# driverLED.net
KiCad netlist of a schematic drawn in EAGLE
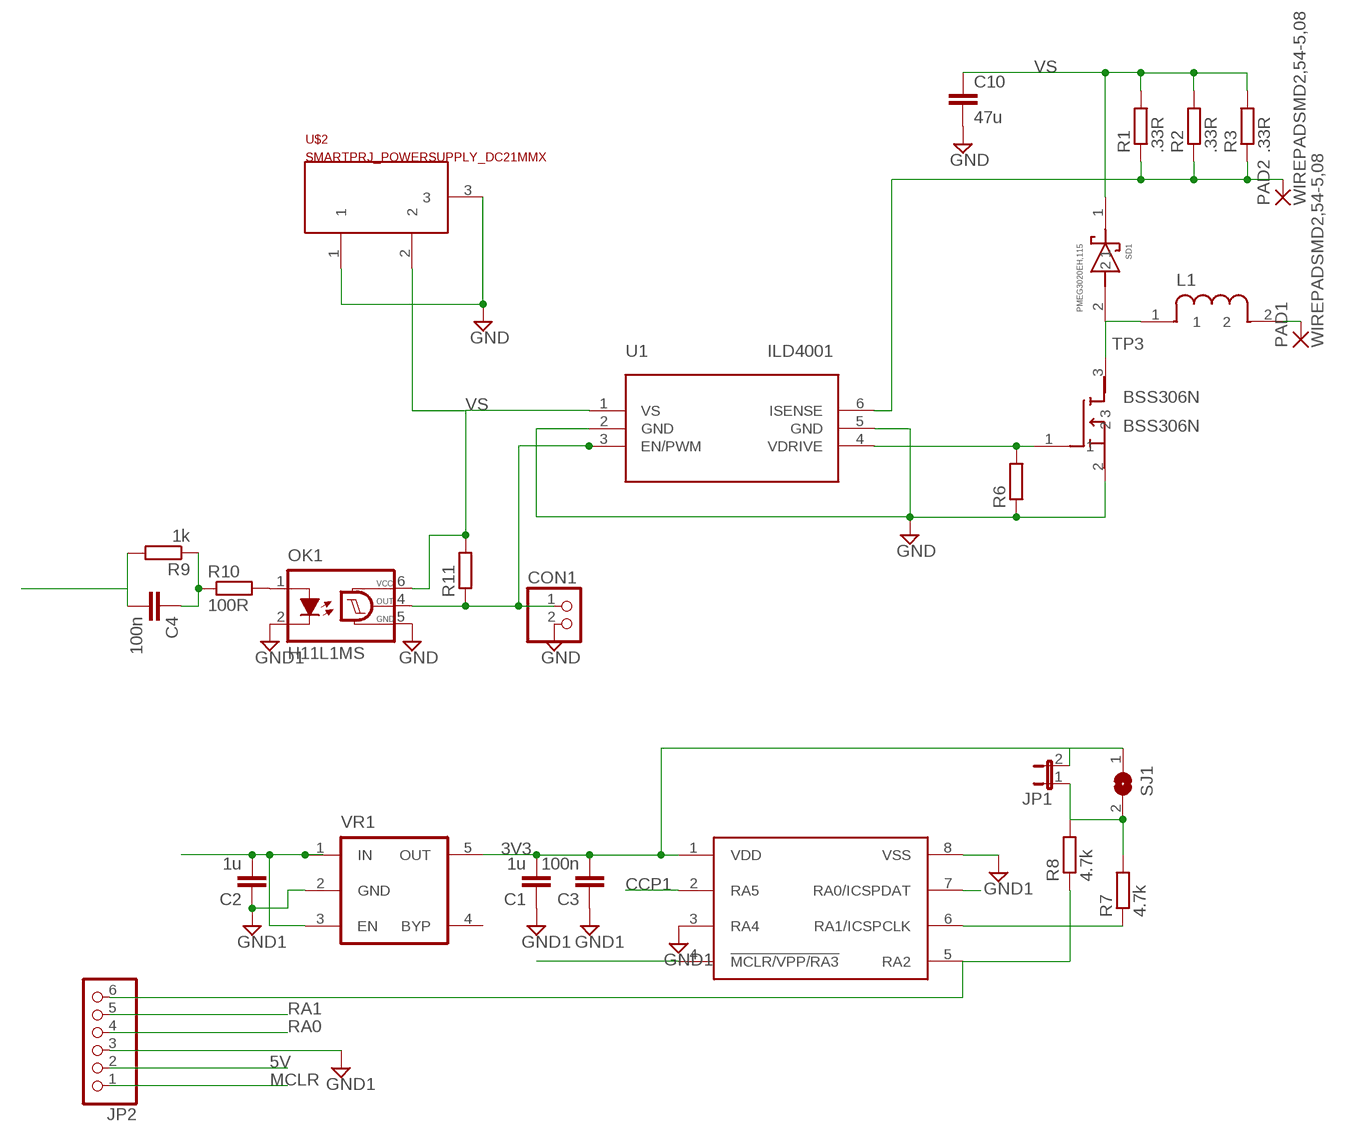
[diagram p0: schematic, sheet 1]

(export (version "E")
  (design (tool "Eeschema 10.0.6"))
  (components
    (comp (ref "BSS306N")
      (value "BSS306N")
      (footprint "eagle-import:SOT23")
      (libsource (lib "eagle-import") (part "BSS306N"))
    )
    (comp (ref "C1")
      (value "1u")
      (footprint "eagle-import:C0603")
      (libsource (lib "eagle-import") (part "C-EUC0603"))
    )
    (comp (ref "C2")
      (value "1u")
      (footprint "eagle-import:C0603")
      (libsource (lib "eagle-import") (part "C-EUC0603"))
    )
    (comp (ref "C3")
      (value "100n")
      (footprint "eagle-import:C0603")
      (libsource (lib "eagle-import") (part "C-EUC0603"))
    )
    (comp (ref "C4")
      (value "100n")
      (footprint "eagle-import:C0603")
      (libsource (lib "eagle-import") (part "C-EUC0603"))
    )
    (comp (ref "C10")
      (value "47u")
      (footprint "eagle-import:C1812")
      (libsource (lib "eagle-import") (part "C-EUC1812"))
    )
    (comp (ref "CON1")
      (value "PINHD-1X2")
      (footprint "eagle-import:1X02")
      (libsource (lib "eagle-import") (part "PINHD-1X2"))
    )
    (comp (ref "JP1")
      (value "JUMPER-2PTH")
      (footprint "eagle-import:1X02")
      (libsource (lib "eagle-import") (part "JUMPER-2PTH"))
    )
    (comp (ref "JP2")
      (value "PINHD-1X6")
      (footprint "eagle-import:1X06")
      (libsource (lib "eagle-import") (part "PINHD-1X6"))
    )
    (comp (ref "L1")
      (value "NR10050T470M")
      (footprint "eagle-import:NR10050T470M")
      (libsource (lib "eagle-import") (part "NR10050T470M"))
    )
    (comp (ref "OK1")
      (value "H11L1MS")
      (footprint "eagle-import:DIL6-SMD")
      (libsource (lib "eagle-import") (part "H11LMS1"))
    )
    (comp (ref "PAD1")
      (value "WIREPADSMD2,54-5,08")
      (footprint "eagle-import:SMD2,54-5,08")
      (libsource (lib "eagle-import") (part "WIREPADSMD2,54-5,08"))
    )
    (comp (ref "PAD2")
      (value "WIREPADSMD2,54-5,08")
      (footprint "eagle-import:SMD2,54-5,08")
      (libsource (lib "eagle-import") (part "WIREPADSMD2,54-5,08"))
    )
    (comp (ref "R1")
      (value ".33R")
      (footprint "eagle-import:R1206")
      (libsource (lib "eagle-import") (part "R-EU_R1206"))
    )
    (comp (ref "R2")
      (value ".33R")
      (footprint "eagle-import:R1206")
      (libsource (lib "eagle-import") (part "R-EU_R1206"))
    )
    (comp (ref "R3")
      (value ".33R")
      (footprint "eagle-import:R1206")
      (libsource (lib "eagle-import") (part "R-EU_R1206"))
    )
    (comp (ref "R6")
      (value "R-EU_R0603")
      (footprint "eagle-import:R0603")
      (libsource (lib "eagle-import") (part "resistor_R-EU_R0603"))
    )
    (comp (ref "R7")
      (value "4.7k")
      (footprint "eagle-import:R0603")
      (libsource (lib "eagle-import") (part "resistor_R-EU_R0603"))
    )
    (comp (ref "R8")
      (value "4.7k")
      (footprint "eagle-import:R0603")
      (libsource (lib "eagle-import") (part "resistor_R-EU_R0603"))
    )
    (comp (ref "R9")
      (value "1k")
      (footprint "eagle-import:R0603")
      (libsource (lib "eagle-import") (part "resistor_R-EU_R0603"))
    )
    (comp (ref "R10")
      (value "100R")
      (footprint "eagle-import:R0603")
      (libsource (lib "eagle-import") (part "R-EU_R0603"))
    )
    (comp (ref "R11")
      (value "R-EU_R0603")
      (footprint "eagle-import:R0603")
      (libsource (lib "eagle-import") (part "resistor_R-EU_R0603"))
    )
    (comp (ref "SD1")
      (value "PMEG3020EH,115")
      (footprint "eagle-import:SOD123F")
      (libsource (lib "eagle-import") (part "PMEG3020EH,115"))
    )
    (comp (ref "SJ1")
      (value "JUMPER_SJ")
      (footprint "eagle-import:JUMPER_SJ")
      (libsource (lib "eagle-import") (part "JUMPER_SJ"))
    )
    (comp (ref "U$1")
      (value "PIC12F1822")
      (footprint "eagle-import:8-SOIC")
      (libsource (lib "eagle-import") (part "PIC12F1822"))
    )
    (comp (ref "U$2")
      (value "SMARTPRJ_POWERSUPPLY_DC21MMX")
      (footprint "eagle-import:SMARTPRJ_POWERSUPPLY_DC-21MM")
      (libsource (lib "eagle-import") (part "SMARTPRJ_POWERSUPPLY_DC21MMX"))
    )
    (comp (ref "U1")
      (value "ILD4001")
      (footprint "eagle-import:SC74")
      (libsource (lib "eagle-import") (part "ILD4001"))
    )
    (comp (ref "VR1")
      (value "MIC5205")
      (footprint "eagle-import:SOT-23-5")
      (libsource (lib "eagle-import") (part "MIC5205"))
    )
  )
  (nets
    (net (code "1") (name "/3V3") (class "Default")
      (node (ref "C1") (pin "2") (pinfunction "2_2") (pintype "passive"))
      (node (ref "C3") (pin "2") (pinfunction "2_2") (pintype "passive"))
      (node (ref "JP1") (pin "2") (pinfunction "2_2") (pintype "passive"))
      (node (ref "SJ1") (pin "1") (pinfunction "1_1") (pintype "passive"))
      (node (ref "U$1") (pin "1") (pinfunction "VDD_1") (pintype "bidirectional"))
      (node (ref "VR1") (pin "5") (pinfunction "OUT_5") (pintype "bidirectional"))
    )
    (net (code "2") (name "/5V") (class "Default")
      (node (ref "C2") (pin "2") (pinfunction "2_2") (pintype "passive"))
      (node (ref "JP2") (pin "2") (pinfunction "2_2") (pintype "passive"))
      (node (ref "VR1") (pin "1") (pinfunction "IN_1") (pintype "bidirectional"))
      (node (ref "VR1") (pin "3") (pinfunction "EN_3") (pintype "bidirectional"))
    )
    (net (code "3") (name "/CCP1") (class "Default")
      (node (ref "C4") (pin "2") (pinfunction "2_2") (pintype "passive"))
      (node (ref "R9") (pin "2") (pinfunction "2_2") (pintype "passive"))
      (node (ref "U$1") (pin "2") (pinfunction "RA5_2") (pintype "bidirectional"))
    )
    (net (code "4") (name "/MCLR") (class "Default")
      (node (ref "JP2") (pin "1") (pinfunction "1_1") (pintype "passive"))
      (node (ref "U$1") (pin "4") (pinfunction "~{MCLR/VPP/RA3}_4") (pintype "bidirectional"))
    )
    (net (code "5") (name "/RA0") (class "Default")
      (node (ref "JP2") (pin "4") (pinfunction "4_4") (pintype "passive"))
      (node (ref "U$1") (pin "7") (pinfunction "RA0/ICSPDAT_7") (pintype "bidirectional"))
    )
    (net (code "6") (name "/RA1") (class "Default")
      (node (ref "JP2") (pin "5") (pinfunction "5_5") (pintype "passive"))
      (node (ref "R7") (pin "1") (pinfunction "1_1") (pintype "passive"))
      (node (ref "U$1") (pin "6") (pinfunction "RA1/ICSPCLK_6") (pintype "bidirectional"))
    )
    (net (code "7") (name "/TP3") (class "Default")
      (node (ref "BSS306N") (pin "3") (pinfunction "3_3") (pintype "bidirectional"))
      (node (ref "L1") (pin "1") (pinfunction "1_1") (pintype "bidirectional"))
      (node (ref "SD1") (pin "2") (pinfunction "2_2") (pintype "bidirectional"))
    )
    (net (code "8") (name "/VS") (class "Default")
      (node (ref "C10") (pin "1") (pinfunction "1_1") (pintype "passive"))
      (node (ref "OK1") (pin "6") (pinfunction "VCC_6") (pintype "power_in"))
      (node (ref "R1") (pin "2") (pinfunction "2_2") (pintype "passive"))
      (node (ref "R11") (pin "2") (pinfunction "2_2") (pintype "passive"))
      (node (ref "R2") (pin "2") (pinfunction "2_2") (pintype "passive"))
      (node (ref "R3") (pin "2") (pinfunction "2_2") (pintype "passive"))
      (node (ref "SD1") (pin "1") (pinfunction "1_1") (pintype "bidirectional"))
      (node (ref "U$2") (pin "2") (pinfunction "2_2") (pintype "power_in"))
      (node (ref "U1") (pin "1") (pinfunction "VS_1") (pintype "bidirectional"))
    )
    (net (code "9") (name "GND") (class "Default")
      (node (ref "BSS306N") (pin "2") (pinfunction "2_2") (pintype "bidirectional"))
      (node (ref "C10") (pin "2") (pinfunction "2_2") (pintype "passive"))
      (node (ref "CON1") (pin "2") (pinfunction "2_2") (pintype "passive"))
      (node (ref "OK1") (pin "5") (pinfunction "GND_5") (pintype "power_in"))
      (node (ref "R6") (pin "1") (pinfunction "1_1") (pintype "passive"))
      (node (ref "U$2") (pin "1") (pinfunction "1_1") (pintype "power_in"))
      (node (ref "U$2") (pin "3") (pinfunction "3_3") (pintype "power_in"))
      (node (ref "U1") (pin "2") (pinfunction "GND_2") (pintype "bidirectional"))
      (node (ref "U1") (pin "5") (pinfunction "GND_5") (pintype "bidirectional"))
    )
    (net (code "10") (name "GND1") (class "Default")
      (node (ref "C1") (pin "1") (pinfunction "1_1") (pintype "passive"))
      (node (ref "C2") (pin "1") (pinfunction "1_1") (pintype "passive"))
      (node (ref "C3") (pin "1") (pinfunction "1_1") (pintype "passive"))
      (node (ref "JP2") (pin "3") (pinfunction "3_3") (pintype "passive"))
      (node (ref "OK1") (pin "2") (pinfunction "C_2") (pintype "passive"))
      (node (ref "U$1") (pin "3") (pinfunction "RA4_3") (pintype "bidirectional"))
      (node (ref "U$1") (pin "8") (pinfunction "VSS_8") (pintype "bidirectional"))
      (node (ref "VR1") (pin "2") (pinfunction "GND_2") (pintype "bidirectional"))
    )
    (net (code "11") (name "Net-(C4-Pad1)") (class "Default")
      (node (ref "C4") (pin "1") (pinfunction "1_1") (pintype "passive"))
      (node (ref "R10") (pin "1") (pinfunction "1_1") (pintype "passive"))
      (node (ref "R9") (pin "1") (pinfunction "1_1") (pintype "passive"))
    )
    (net (code "12") (name "Net-(JP1-Pad1)") (class "Default")
      (node (ref "JP1") (pin "1") (pinfunction "1_1") (pintype "passive"))
      (node (ref "R7") (pin "2") (pinfunction "2_2") (pintype "passive"))
      (node (ref "R8") (pin "2") (pinfunction "2_2") (pintype "passive"))
      (node (ref "SJ1") (pin "2") (pinfunction "2_2") (pintype "passive"))
    )
    (net (code "13") (name "Net-(OK1-A)") (class "Default")
      (node (ref "OK1") (pin "1") (pinfunction "A_1") (pintype "passive"))
      (node (ref "R10") (pin "2") (pinfunction "2_2") (pintype "passive"))
    )
    (net (code "14") (name "Net-(OK1-OUT)") (class "Default")
      (node (ref "CON1") (pin "1") (pinfunction "1_1") (pintype "passive"))
      (node (ref "OK1") (pin "4") (pinfunction "OUT_4") (pintype "output"))
      (node (ref "R11") (pin "1") (pinfunction "1_1") (pintype "passive"))
      (node (ref "U1") (pin "3") (pinfunction "EN/PWM_3") (pintype "bidirectional"))
    )
    (net (code "15") (name "Net-(PAD1-P)") (class "Default")
      (node (ref "L1") (pin "2") (pinfunction "2_2") (pintype "bidirectional"))
      (node (ref "PAD1") (pin "1") (pinfunction "P_1") (pintype "passive"))
    )
    (net (code "16") (name "Net-(PAD2-P)") (class "Default")
      (node (ref "PAD2") (pin "1") (pinfunction "P_1") (pintype "passive"))
      (node (ref "R1") (pin "1") (pinfunction "1_1") (pintype "passive"))
      (node (ref "R2") (pin "1") (pinfunction "1_1") (pintype "passive"))
      (node (ref "R3") (pin "1") (pinfunction "1_1") (pintype "passive"))
      (node (ref "U1") (pin "6") (pinfunction "ISENSE_6") (pintype "bidirectional"))
    )
    (net (code "17") (name "Net-(U$1-RA2)") (class "Default")
      (node (ref "JP2") (pin "6") (pinfunction "6_6") (pintype "passive"))
      (node (ref "R8") (pin "1") (pinfunction "1_1") (pintype "passive"))
      (node (ref "U$1") (pin "5") (pinfunction "RA2_5") (pintype "bidirectional"))
    )
    (net (code "18") (name "Net-(U1-VDRIVE)") (class "Default")
      (node (ref "BSS306N") (pin "1") (pinfunction "1_1") (pintype "bidirectional"))
      (node (ref "R6") (pin "2") (pinfunction "2_2") (pintype "passive"))
      (node (ref "U1") (pin "4") (pinfunction "VDRIVE_4") (pintype "bidirectional"))
    )
    (net (code "19") (name "unconnected-(VR1-BYP-Pad4)") (class "Default")
      (node (ref "VR1") (pin "4") (pinfunction "BYP_4") (pintype "bidirectional"))
    )
  )
)
